# start.net
KiCad netlist of a schematic drawn in Altium Designer
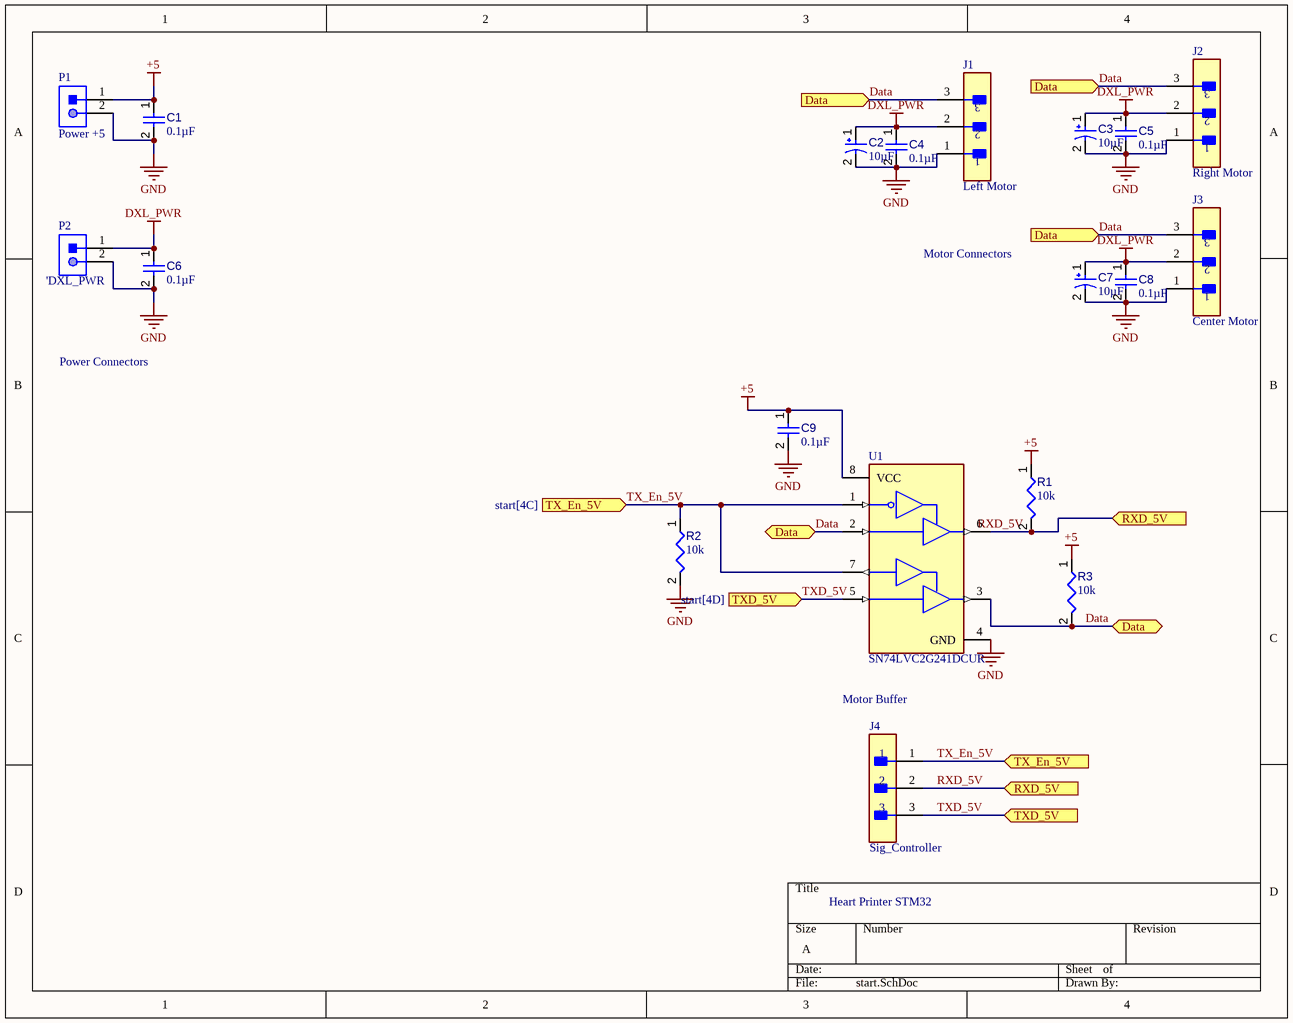
[diagram p0: start.SchDoc]

(export (version "E")
  (design (tool "Eeschema 10.0.6"))
  (components
    (comp (ref "C1")
      (value "0.1µF")
      (footprint "CAPC1005X55X25ML5T10")
      (description "Chip Capacitor, 1 uF, +/- 10%, 6.3 V, 1005 (0402 Metric)")
      (fields (field (name "TOLERANCE") "10%") (field (name "Comment") "Capacitor 1 uF +/- 10% 6.3 V 1005"))
      (libsource (lib "Shreyas Sanghvi") (part "CAP-NP-2"))
    )
    (comp (ref "C2")
      (value "10µF")
      (footprint "CAPPR55-200-1100X500X1200")
      (description "Aluminum Electrolytic Capacitor, 2.2 uF, +/- 20%, 50 V, -40 to 85 degC, 2-Pin THD, RoHS, Bulk")
      (fields (field (name "TOLERANCE") "20%") (field (name "MANUFACTURER") "Panasonic"))
      (libsource (lib "Shreyas Sanghvi") (part "CAP-P-2"))
    )
    (comp (ref "C3")
      (value "10µF")
      (footprint "CAPPR55-200-1100X500X1200")
      (description "Aluminum Electrolytic Capacitor, 2.2 uF, +/- 20%, 50 V, -40 to 85 degC, 2-Pin THD, RoHS, Bulk")
      (fields (field (name "TOLERANCE") "20%") (field (name "MANUFACTURER") "Panasonic"))
      (libsource (lib "Shreyas Sanghvi") (part "CAP-P-2"))
    )
    (comp (ref "C4")
      (value "0.1µF")
      (footprint "CAPC1005X55X25ML5T10")
      (description "Chip Capacitor, 1 uF, +/- 10%, 6.3 V, 1005 (0402 Metric)")
      (fields (field (name "TOLERANCE") "10%") (field (name "Comment") "Capacitor 1 uF +/- 10% 6.3 V 1005"))
      (libsource (lib "Shreyas Sanghvi") (part "CAP-NP-2"))
    )
    (comp (ref "C5")
      (value "0.1µF")
      (footprint "CAPC1005X55X25ML5T10")
      (description "Chip Capacitor, 1 uF, +/- 10%, 6.3 V, 1005 (0402 Metric)")
      (fields (field (name "TOLERANCE") "10%") (field (name "Comment") "Capacitor 1 uF +/- 10% 6.3 V 1005"))
      (libsource (lib "Shreyas Sanghvi") (part "CAP-NP-2"))
    )
    (comp (ref "C6")
      (value "0.1µF")
      (footprint "CAPC1005X55X25ML5T10")
      (description "Chip Capacitor, 1 uF, +/- 10%, 6.3 V, 1005 (0402 Metric)")
      (fields (field (name "TOLERANCE") "10%") (field (name "Comment") "Capacitor 1 uF +/- 10% 6.3 V 1005"))
      (libsource (lib "Shreyas Sanghvi") (part "CAP-NP-2"))
    )
    (comp (ref "C7")
      (value "10µF")
      (footprint "CAPPR55-200-1100X500X1200")
      (description "Aluminum Electrolytic Capacitor, 2.2 uF, +/- 20%, 50 V, -40 to 85 degC, 2-Pin THD, RoHS, Bulk")
      (fields (field (name "TOLERANCE") "20%") (field (name "MANUFACTURER") "Panasonic"))
      (libsource (lib "Shreyas Sanghvi") (part "CAP-P-2"))
    )
    (comp (ref "C8")
      (value "0.1µF")
      (footprint "CAPC1005X55X25ML5T10")
      (description "Chip Capacitor, 1 uF, +/- 10%, 6.3 V, 1005 (0402 Metric)")
      (fields (field (name "TOLERANCE") "10%") (field (name "Comment") "Capacitor 1 uF +/- 10% 6.3 V 1005"))
      (libsource (lib "Shreyas Sanghvi") (part "CAP-NP-2"))
    )
    (comp (ref "C9")
      (value "0.1µF")
      (footprint "CAPC1005X55X25ML5T10")
      (description "Chip Capacitor, 1 uF, +/- 10%, 6.3 V, 1005 (0402 Metric)")
      (fields (field (name "TOLERANCE") "10%") (field (name "Comment") "Capacitor 1 uF +/- 10% 6.3 V 1005"))
      (libsource (lib "Shreyas Sanghvi") (part "CAP-NP-2"))
    )
    (comp (ref "J1")
      (value "Left Motor")
      (footprint "FP-B3B-ZR_LF_SN-MFG")
      (description "CONN HEADER VERT 3POS 1.5MM")
      (libsource (lib "Altium Content Vault") (part "0d3f023dd272f625e17a2be33dea85f"))
    )
    (comp (ref "J2")
      (value "Right Motor")
      (footprint "FP-B3B-ZR_LF_SN-MFG")
      (description "CONN HEADER VERT 3POS 1.5MM")
      (libsource (lib "Altium Content Vault") (part "0d3f023dd272f625e17a2be33dea85f"))
    )
    (comp (ref "J3")
      (value "Center Motor")
      (footprint "FP-B3B-ZR_LF_SN-MFG")
      (description "CONN HEADER VERT 3POS 1.5MM")
      (libsource (lib "Altium Content Vault") (part "0d3f023dd272f625e17a2be33dea85f"))
    )
    (comp (ref "J4")
      (value "Sig_Controller")
      (footprint "FP-B3B-ZR_LF_SN-MFG")
      (description "CONN HEADER VERT 3POS 1.5MM")
      (libsource (lib "") (part "0d3f023dd272f625e17a2be33dea85f_1"))
    )
    (comp (ref "P1")
      (value "Power +5")
      (footprint "JST-S2B-XH-A(LF)(SN)_V")
      (fields (field (name "TOLERANCE") "10%"))
      (libsource (lib "Altium Content Vault") (part "CN-1P-M-R2"))
    )
    (comp (ref "P2")
      (value "'DXL_PWR")
      (footprint "JST-S2B-XH-A(LF)(SN)_V")
      (fields (field (name "TOLERANCE") "10%"))
      (libsource (lib "Altium Content Vault") (part "CN-1P-M-R2"))
    )
    (comp (ref "R1")
      (value "10k")
      (footprint "RESC3216X60X45ML15T20")
      (description "Chip Resistor, 10 KOhm, +/- 1%, 0.25 W, -55 to 155 degC, 1206 (3216 Metric)")
      (fields (field (name "TOLERANCE") "1%") (field (name "POWER") "250mW"))
      (libsource (lib "Shreyas Sanghvi") (part "RES-2"))
    )
    (comp (ref "R2")
      (value "10k")
      (footprint "RESC3216X60X45ML15T20")
      (description "Chip Resistor, 10 KOhm, +/- 1%, 0.25 W, -55 to 155 degC, 1206 (3216 Metric)")
      (fields (field (name "TOLERANCE") "1%") (field (name "POWER") "250mW"))
      (libsource (lib "Shreyas Sanghvi") (part "RES-2"))
    )
    (comp (ref "R3")
      (value "10k")
      (footprint "RESC3216X60X45ML15T20")
      (description "Chip Resistor, 10 KOhm, +/- 1%, 0.25 W, -55 to 155 degC, 1206 (3216 Metric)")
      (fields (field (name "TOLERANCE") "1%") (field (name "POWER") "250mW"))
      (libsource (lib "Shreyas Sanghvi") (part "RES-2"))
    )
    (comp (ref "U1")
      (value "SN74LVC2G241DCUR")
      (footprint "FP-DCU0008A-MFG")
      (description "IC BUFFER NON-INVERT 5.5V US8")
      (fields
        (field (name "OCTOPART") "https://octopart.com/sn74lvc2g241dcur-texas+instruments-422866")
        (field (name "MANUFACTURER") "Texas Instruments")
      )
      (libsource (lib "Altium Content Vault") (part "bd99d9f473bc4d41df3fcbef237a47a"))
    )
  )
  (nets
    (net (code "1") (name "+5") (class "Default")
      (node (ref "C1") (pin "1") (pinfunction "1_1") (pintype "passive"))
      (node (ref "C9") (pin "1") (pinfunction "1_1") (pintype "passive"))
      (node (ref "P1") (pin "1") (pinfunction "1_1") (pintype "passive"))
      (node (ref "R1") (pin "1") (pinfunction "1_1") (pintype "passive"))
      (node (ref "R3") (pin "1") (pinfunction "1_1") (pintype "passive"))
      (node (ref "U1") (pin "8") (pinfunction "VCC_8") (pintype "power_in"))
    )
    (net (code "2") (name "/Data") (class "Default")
      (node (ref "J1") (pin "3") (pinfunction "3_3") (pintype "passive"))
      (node (ref "J2") (pin "3") (pinfunction "3_3") (pintype "passive"))
      (node (ref "J3") (pin "3") (pinfunction "3_3") (pintype "passive"))
      (node (ref "R3") (pin "2") (pinfunction "2_2") (pintype "passive"))
      (node (ref "U1") (pin "2") (pinfunction "1A_2") (pintype "input"))
      (node (ref "U1") (pin "3") (pinfunction "2Y_3") (pintype "output"))
    )
    (net (code "3") (name "/RXD_5V") (class "Default")
      (node (ref "J4") (pin "2") (pinfunction "2_2") (pintype "passive"))
      (node (ref "R1") (pin "2") (pinfunction "2_2") (pintype "passive"))
      (node (ref "U1") (pin "6") (pinfunction "1Y_6") (pintype "output"))
    )
    (net (code "4") (name "/TXD_5V") (class "Default")
      (node (ref "J4") (pin "3") (pinfunction "3_3") (pintype "passive"))
      (node (ref "U1") (pin "5") (pinfunction "2A_5") (pintype "input"))
    )
    (net (code "5") (name "/TX_En_5V") (class "Default")
      (node (ref "J4") (pin "1") (pinfunction "1_1") (pintype "passive"))
      (node (ref "R2") (pin "1") (pinfunction "1_1") (pintype "passive"))
      (node (ref "U1") (pin "1") (pinfunction "1~{OE}_1") (pintype "input"))
      (node (ref "U1") (pin "7") (pinfunction "2OE_7") (pintype "output"))
    )
    (net (code "6") (name "DXL_PWR") (class "Default")
      (node (ref "C2") (pin "1") (pinfunction "1_1") (pintype "passive"))
      (node (ref "C3") (pin "1") (pinfunction "1_1") (pintype "passive"))
      (node (ref "C4") (pin "1") (pinfunction "1_1") (pintype "passive"))
      (node (ref "C5") (pin "1") (pinfunction "1_1") (pintype "passive"))
      (node (ref "C6") (pin "1") (pinfunction "1_1") (pintype "passive"))
      (node (ref "C7") (pin "1") (pinfunction "1_1") (pintype "passive"))
      (node (ref "C8") (pin "1") (pinfunction "1_1") (pintype "passive"))
      (node (ref "J1") (pin "2") (pinfunction "2_2") (pintype "passive"))
      (node (ref "J2") (pin "2") (pinfunction "2_2") (pintype "passive"))
      (node (ref "J3") (pin "2") (pinfunction "2_2") (pintype "passive"))
      (node (ref "P2") (pin "1") (pinfunction "1_1") (pintype "passive"))
    )
    (net (code "7") (name "GND") (class "Default")
      (node (ref "C1") (pin "2") (pinfunction "2_2") (pintype "passive"))
      (node (ref "C2") (pin "2") (pinfunction "2_2") (pintype "passive"))
      (node (ref "C3") (pin "2") (pinfunction "2_2") (pintype "passive"))
      (node (ref "C4") (pin "2") (pinfunction "2_2") (pintype "passive"))
      (node (ref "C5") (pin "2") (pinfunction "2_2") (pintype "passive"))
      (node (ref "C6") (pin "2") (pinfunction "2_2") (pintype "passive"))
      (node (ref "C7") (pin "2") (pinfunction "2_2") (pintype "passive"))
      (node (ref "C8") (pin "2") (pinfunction "2_2") (pintype "passive"))
      (node (ref "C9") (pin "2") (pinfunction "2_2") (pintype "passive"))
      (node (ref "J1") (pin "1") (pinfunction "1_1") (pintype "passive"))
      (node (ref "J2") (pin "1") (pinfunction "1_1") (pintype "passive"))
      (node (ref "J3") (pin "1") (pinfunction "1_1") (pintype "passive"))
      (node (ref "P1") (pin "2") (pinfunction "2_2") (pintype "passive"))
      (node (ref "P2") (pin "2") (pinfunction "2_2") (pintype "passive"))
      (node (ref "R2") (pin "2") (pinfunction "2_2") (pintype "passive"))
      (node (ref "U1") (pin "4") (pinfunction "GND_4") (pintype "power_in"))
    )
  )
)
